# driverCorriente.net
KiCad netlist of a schematic drawn in EAGLE
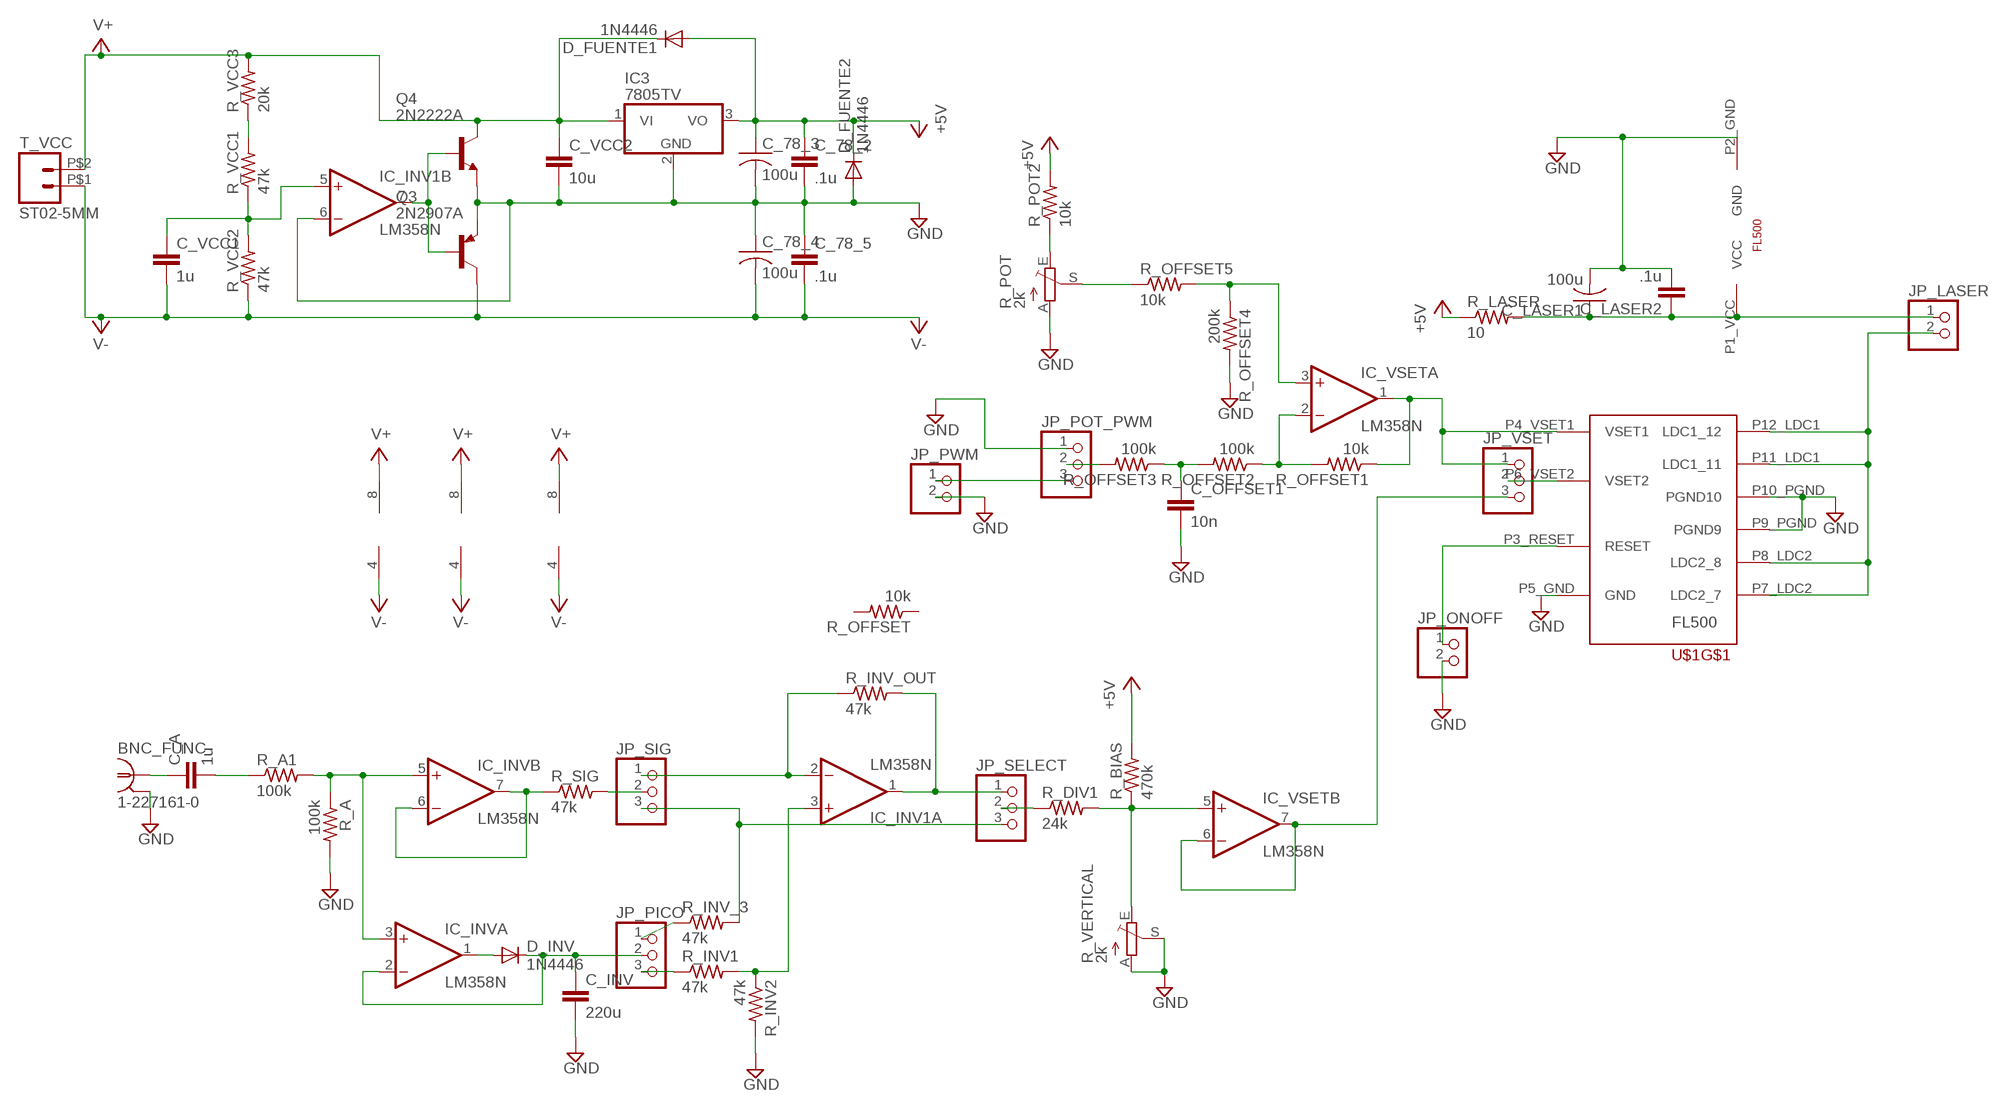
[diagram p0: schematic, sheet 1]

(export (version "E")
  (design (tool "Eeschema 10.0.6"))
  (components
    (comp (ref "BNC_FUNC")
      (value "1-227161-0")
      (footprint "eagle-import:AMP_227161")
      (fields (field (name "MF") "TYCO ELECTRONICS") (field (name "MPN") "1-227161"))
      (libsource (lib "eagle-import") (part "?2271611--0"))
    )
    (comp (ref "C_78_2")
      (value ".1u")
      (footprint "eagle-import:C050-045X075")
      (libsource (lib "eagle-import") (part "C-EU050-045X075"))
    )
    (comp (ref "C_78_3")
      (value "100u")
      (footprint "eagle-import:C050-075X075")
      (libsource (lib "eagle-import") (part "C-US050-075X075"))
    )
    (comp (ref "C_78_4")
      (value "100u")
      (footprint "eagle-import:C050-075X075")
      (libsource (lib "eagle-import") (part "C-US050-075X075"))
    )
    (comp (ref "C_78_5")
      (value ".1u")
      (footprint "eagle-import:C050-045X075")
      (libsource (lib "eagle-import") (part "C-EU050-045X075"))
    )
    (comp (ref "C_A")
      (value "1u")
      (footprint "eagle-import:C050-045X075")
      (libsource (lib "eagle-import") (part "C-EU050-045X075"))
    )
    (comp (ref "C_INV")
      (value "220u")
      (footprint "eagle-import:C050-045X075")
      (libsource (lib "eagle-import") (part "C-EU050-045X075"))
    )
    (comp (ref "C_LASER1")
      (value "100u")
      (footprint "eagle-import:C050-075X075")
      (libsource (lib "eagle-import") (part "C-US050-075X075"))
    )
    (comp (ref "C_LASER2")
      (value ".1u")
      (footprint "eagle-import:C050-045X075")
      (libsource (lib "eagle-import") (part "C-EU050-045X075"))
    )
    (comp (ref "C_OFFSET1")
      (value "10n")
      (footprint "eagle-import:C050-045X075")
      (libsource (lib "eagle-import") (part "C-EU050-045X075"))
    )
    (comp (ref "C_VCC1")
      (value "1u")
      (footprint "eagle-import:C050-045X075")
      (libsource (lib "eagle-import") (part "C-EU050-045X075"))
    )
    (comp (ref "C_VCC2")
      (value "10u")
      (footprint "eagle-import:C050-045X075")
      (libsource (lib "eagle-import") (part "C-EU050-045X075"))
    )
    (comp (ref "D_FUENTE1")
      (value "1N4446")
      (footprint "eagle-import:DO35-10")
      (libsource (lib "eagle-import") (part "1N4446"))
    )
    (comp (ref "D_FUENTE2")
      (value "1N4446")
      (footprint "eagle-import:DO35-10")
      (libsource (lib "eagle-import") (part "1N4446"))
    )
    (comp (ref "D_INV")
      (value "1N4446")
      (footprint "eagle-import:DO35-10")
      (libsource (lib "eagle-import") (part "1N4446"))
    )
    (comp (ref "IC3")
      (value "7805TV")
      (footprint "eagle-import:TO220V")
      (libsource (lib "eagle-import") (part "78TV05"))
    )
    (comp (ref "IC_INV")
      (value "LM358N")
      (footprint "eagle-import:DIL08")
      (libsource (lib "eagle-import") (part "LM358N"))
    )
    (comp (ref "IC_INV1")
      (value "LM358N")
      (footprint "eagle-import:DIL08")
      (libsource (lib "eagle-import") (part "LM358N"))
    )
    (comp (ref "IC_VSET")
      (value "LM358N")
      (footprint "eagle-import:DIL08")
      (libsource (lib "eagle-import") (part "LM358N"))
    )
    (comp (ref "JP_LASER")
      (value "PINHD-1X2")
      (footprint "eagle-import:1X02")
      (libsource (lib "eagle-import") (part "PINHD-1X2"))
    )
    (comp (ref "JP_ONOFF")
      (value "PINHD-1X2")
      (footprint "eagle-import:1X02")
      (libsource (lib "eagle-import") (part "PINHD-1X2"))
    )
    (comp (ref "JP_PICO")
      (value "PINHD-1X3")
      (footprint "eagle-import:1X03")
      (libsource (lib "eagle-import") (part "PINHD-1X3"))
    )
    (comp (ref "JP_POT_PWM")
      (value "PINHD-1X3")
      (footprint "eagle-import:1X03")
      (libsource (lib "eagle-import") (part "PINHD-1X3"))
    )
    (comp (ref "JP_PWM")
      (value "PINHD-1X2")
      (footprint "eagle-import:1X02")
      (libsource (lib "eagle-import") (part "PINHD-1X2"))
    )
    (comp (ref "JP_SELECT")
      (value "PINHD-1X3")
      (footprint "eagle-import:1X03")
      (libsource (lib "eagle-import") (part "PINHD-1X3"))
    )
    (comp (ref "JP_SIG")
      (value "PINHD-1X3")
      (footprint "eagle-import:1X03")
      (libsource (lib "eagle-import") (part "PINHD-1X3"))
    )
    (comp (ref "JP_VSET")
      (value "PINHD-1X3")
      (footprint "eagle-import:1X03")
      (libsource (lib "eagle-import") (part "PINHD-1X3"))
    )
    (comp (ref "Q3")
      (value "2N2907A")
      (footprint "eagle-import:TO18")
      (libsource (lib "eagle-import") (part "2N2907A"))
    )
    (comp (ref "Q4")
      (value "2N2222A")
      (footprint "eagle-import:TO18")
      (libsource (lib "eagle-import") (part "2N2222A"))
    )
    (comp (ref "R_A")
      (value "100k")
      (footprint "eagle-import:0207_12")
      (libsource (lib "eagle-import") (part "R-US_0207/12"))
    )
    (comp (ref "R_A1")
      (value "100k")
      (footprint "eagle-import:0207_12")
      (libsource (lib "eagle-import") (part "R-US_0207/12"))
    )
    (comp (ref "R_BIAS")
      (value "470k")
      (footprint "eagle-import:0207_12")
      (libsource (lib "eagle-import") (part "R-US_0207/12"))
    )
    (comp (ref "R_DIV1")
      (value "24k")
      (footprint "eagle-import:0207_12")
      (libsource (lib "eagle-import") (part "R-US_0207/12"))
    )
    (comp (ref "R_INV1")
      (value "47k")
      (footprint "eagle-import:0207_12")
      (libsource (lib "eagle-import") (part "R-US_0207/12"))
    )
    (comp (ref "R_INV2")
      (value "47k")
      (footprint "eagle-import:0207_12")
      (libsource (lib "eagle-import") (part "R-US_0207/12"))
    )
    (comp (ref "R_INV_3")
      (value "47k")
      (footprint "eagle-import:0207_12")
      (libsource (lib "eagle-import") (part "R-US_0207/12"))
    )
    (comp (ref "R_INV_OUT")
      (value "47k")
      (footprint "eagle-import:0207_12")
      (libsource (lib "eagle-import") (part "R-US_0207/12"))
    )
    (comp (ref "R_LASER")
      (value "10")
      (footprint "eagle-import:0207_12")
      (libsource (lib "eagle-import") (part "R-US_0207/12"))
    )
    (comp (ref "R_OFFSET")
      (value "10k")
      (footprint "eagle-import:0207_12")
      (libsource (lib "eagle-import") (part "R-US_0207/12"))
    )
    (comp (ref "R_OFFSET1")
      (value "10k")
      (footprint "eagle-import:0207_12")
      (libsource (lib "eagle-import") (part "R-US_0207/12"))
    )
    (comp (ref "R_OFFSET2")
      (value "100k")
      (footprint "eagle-import:0207_12")
      (libsource (lib "eagle-import") (part "R-US_0207/12"))
    )
    (comp (ref "R_OFFSET3")
      (value "100k")
      (footprint "eagle-import:0207_12")
      (libsource (lib "eagle-import") (part "R-US_0207/12"))
    )
    (comp (ref "R_OFFSET4")
      (value "200k")
      (footprint "eagle-import:0207_12")
      (libsource (lib "eagle-import") (part "R-US_0207/12"))
    )
    (comp (ref "R_OFFSET5")
      (value "10k")
      (footprint "eagle-import:0207_12")
      (libsource (lib "eagle-import") (part "R-US_0207/12"))
    )
    (comp (ref "R_POT")
      (value "2k")
      (footprint "eagle-import:B64Y")
      (libsource (lib "eagle-import") (part "TRIM_EU-B64Y"))
    )
    (comp (ref "R_POT2")
      (value "10k")
      (footprint "eagle-import:0207_12")
      (libsource (lib "eagle-import") (part "R-US_0207/12"))
    )
    (comp (ref "R_SIG")
      (value "47k")
      (footprint "eagle-import:0207_12")
      (libsource (lib "eagle-import") (part "R-US_0207/12"))
    )
    (comp (ref "R_VCC1")
      (value "47k")
      (footprint "eagle-import:0207_12")
      (libsource (lib "eagle-import") (part "R-US_0207/12"))
    )
    (comp (ref "R_VCC2")
      (value "47k")
      (footprint "eagle-import:0207_12")
      (libsource (lib "eagle-import") (part "R-US_0207/12"))
    )
    (comp (ref "R_VCC3")
      (value "20k")
      (footprint "eagle-import:0207_12")
      (libsource (lib "eagle-import") (part "R-US_0207/12"))
    )
    (comp (ref "R_VERTICAL")
      (value "2k")
      (footprint "eagle-import:B64Y")
      (libsource (lib "eagle-import") (part "TRIM_EU-B64Y"))
    )
    (comp (ref "T_VCC")
      (value "ST02-5MM")
      (footprint "eagle-import:EK500V-02P")
      (libsource (lib "eagle-import") (part "ST02-5MM"))
    )
    (comp (ref "U$1")
      (value "FL500")
      (footprint "eagle-import:FL500")
      (libsource (lib "eagle-import") (part "FL500"))
    )
  )
  (nets
    (net (code "1") (name "+5V") (class "Default")
      (node (ref "C_78_2") (pin "1") (pinfunction "1_1") (pintype "passive"))
      (node (ref "C_78_3") (pin "1") (pinfunction "1_1") (pintype "passive"))
      (node (ref "D_FUENTE1") (pin "A") (pinfunction "A_A") (pintype "passive"))
      (node (ref "D_FUENTE2") (pin "C") (pinfunction "C_C") (pintype "passive"))
      (node (ref "IC3") (pin "3") (pinfunction "VO_3") (pintype "passive"))
      (node (ref "R_BIAS") (pin "2") (pinfunction "2_2") (pintype "passive"))
      (node (ref "R_LASER") (pin "1") (pinfunction "1_1") (pintype "passive"))
      (node (ref "R_POT2") (pin "2") (pinfunction "2_2") (pintype "passive"))
    )
    (net (code "2") (name "GND") (class "Default")
      (node (ref "BNC_FUNC") (pin "2") (pinfunction "2_2") (pintype "passive"))
      (node (ref "C_78_2") (pin "2") (pinfunction "2_2") (pintype "passive"))
      (node (ref "C_78_3") (pin "2") (pinfunction "2_2") (pintype "passive"))
      (node (ref "C_78_4") (pin "1") (pinfunction "1_1") (pintype "passive"))
      (node (ref "C_78_5") (pin "1") (pinfunction "1_1") (pintype "passive"))
      (node (ref "C_INV") (pin "2") (pinfunction "2_2") (pintype "passive"))
      (node (ref "C_LASER1") (pin "2") (pinfunction "2_2") (pintype "passive"))
      (node (ref "C_LASER2") (pin "2") (pinfunction "2_2") (pintype "passive"))
      (node (ref "C_OFFSET1") (pin "2") (pinfunction "2_2") (pintype "passive"))
      (node (ref "C_VCC2") (pin "2") (pinfunction "2_2") (pintype "passive"))
      (node (ref "D_FUENTE2") (pin "A") (pinfunction "A_A") (pintype "passive"))
      (node (ref "IC3") (pin "2") (pinfunction "GND_2") (pintype "passive"))
      (node (ref "IC_INV1") (pin "6") (pinfunction "-IN_6") (pintype "input"))
      (node (ref "JP_ONOFF") (pin "2") (pinfunction "2_2") (pintype "passive"))
      (node (ref "JP_POT_PWM") (pin "1") (pinfunction "1_1") (pintype "passive"))
      (node (ref "JP_PWM") (pin "2") (pinfunction "2_2") (pintype "passive"))
      (node (ref "Q3") (pin "1") (pinfunction "E_1") (pintype "passive"))
      (node (ref "Q4") (pin "1") (pinfunction "E_1") (pintype "passive"))
      (node (ref "R_A") (pin "2") (pinfunction "2_2") (pintype "passive"))
      (node (ref "R_INV2") (pin "2") (pinfunction "2_2") (pintype "passive"))
      (node (ref "R_OFFSET4") (pin "2") (pinfunction "2_2") (pintype "passive"))
      (node (ref "R_POT") (pin "A") (pinfunction "A_A") (pintype "passive"))
      (node (ref "R_VERTICAL") (pin "A") (pinfunction "A_A") (pintype "passive"))
      (node (ref "R_VERTICAL") (pin "S") (pinfunction "S_S") (pintype "passive"))
      (node (ref "U$1") (pin "P10_PGND") (pinfunction "PGND10_P10_PGND") (pintype "bidirectional"))
      (node (ref "U$1") (pin "P2_GND") (pinfunction "GND_P2_GND") (pintype "bidirectional"))
      (node (ref "U$1") (pin "P5_GND") (pinfunction "GND_P5_GND") (pintype "bidirectional"))
      (node (ref "U$1") (pin "P9_PGND") (pinfunction "PGND9_P9_PGND") (pintype "bidirectional"))
    )
    (net (code "3") (name "Net-(BNC_FUNC-Pad1)") (class "Default")
      (node (ref "BNC_FUNC") (pin "1") (pinfunction "1_1") (pintype "passive"))
      (node (ref "C_A") (pin "1") (pinfunction "1_1") (pintype "passive"))
    )
    (net (code "4") (name "Net-(C_A-Pad2)") (class "Default")
      (node (ref "C_A") (pin "2") (pinfunction "2_2") (pintype "passive"))
      (node (ref "R_A1") (pin "1") (pinfunction "1_1") (pintype "passive"))
    )
    (net (code "5") (name "Net-(C_OFFSET1-Pad1)") (class "Default")
      (node (ref "C_OFFSET1") (pin "1") (pinfunction "1_1") (pintype "passive"))
      (node (ref "R_OFFSET2") (pin "2") (pinfunction "2_2") (pintype "passive"))
      (node (ref "R_OFFSET3") (pin "1") (pinfunction "1_1") (pintype "passive"))
    )
    (net (code "6") (name "Net-(IC_INV1A-+IN)") (class "Default")
      (node (ref "IC_INV1") (pin "3") (pinfunction "+IN_3") (pintype "input"))
      (node (ref "R_INV1") (pin "2") (pinfunction "2_2") (pintype "passive"))
      (node (ref "R_INV2") (pin "1") (pinfunction "1_1") (pintype "passive"))
    )
    (net (code "7") (name "Net-(IC_INV1A--IN)") (class "Default")
      (node (ref "IC_INV1") (pin "2") (pinfunction "-IN_2") (pintype "input"))
      (node (ref "JP_SIG") (pin "1") (pinfunction "1_1") (pintype "passive"))
      (node (ref "R_INV_OUT") (pin "1") (pinfunction "1_1") (pintype "passive"))
    )
    (net (code "8") (name "Net-(IC_INV1A-OUT)") (class "Default")
      (node (ref "IC_INV1") (pin "1") (pinfunction "OUT_1") (pintype "output"))
      (node (ref "JP_SELECT") (pin "1") (pinfunction "1_1") (pintype "passive"))
      (node (ref "R_INV_OUT") (pin "2") (pinfunction "2_2") (pintype "passive"))
    )
    (net (code "9") (name "Net-(IC_INV1B-+IN)") (class "Default")
      (node (ref "C_VCC1") (pin "1") (pinfunction "1_1") (pintype "passive"))
      (node (ref "IC_INV1") (pin "5") (pinfunction "+IN_5") (pintype "input"))
      (node (ref "R_VCC1") (pin "1") (pinfunction "1_1") (pintype "passive"))
      (node (ref "R_VCC2") (pin "2") (pinfunction "2_2") (pintype "passive"))
    )
    (net (code "10") (name "Net-(IC_INV1B-OUT)") (class "Default")
      (node (ref "IC_INV1") (pin "7") (pinfunction "OUT_7") (pintype "output"))
      (node (ref "Q3") (pin "2") (pinfunction "B_2") (pintype "passive"))
      (node (ref "Q4") (pin "2") (pinfunction "B_2") (pintype "passive"))
    )
    (net (code "11") (name "Net-(IC_INVA-+IN)") (class "Default")
      (node (ref "IC_INV") (pin "3") (pinfunction "+IN_3") (pintype "input"))
      (node (ref "IC_INV") (pin "5") (pinfunction "+IN_5") (pintype "input"))
      (node (ref "R_A") (pin "1") (pinfunction "1_1") (pintype "passive"))
      (node (ref "R_A1") (pin "2") (pinfunction "2_2") (pintype "passive"))
    )
    (net (code "12") (name "Net-(IC_INVA--IN)") (class "Default")
      (node (ref "C_INV") (pin "1") (pinfunction "1_1") (pintype "passive"))
      (node (ref "D_INV") (pin "C") (pinfunction "C_C") (pintype "passive"))
      (node (ref "IC_INV") (pin "2") (pinfunction "-IN_2") (pintype "input"))
      (node (ref "JP_PICO") (pin "2") (pinfunction "2_2") (pintype "passive"))
    )
    (net (code "13") (name "Net-(IC_INVA-OUT)") (class "Default")
      (node (ref "D_INV") (pin "A") (pinfunction "A_A") (pintype "passive"))
      (node (ref "IC_INV") (pin "1") (pinfunction "OUT_1") (pintype "output"))
    )
    (net (code "14") (name "Net-(IC_INVB--IN)") (class "Default")
      (node (ref "IC_INV") (pin "6") (pinfunction "-IN_6") (pintype "input"))
      (node (ref "IC_INV") (pin "7") (pinfunction "OUT_7") (pintype "output"))
      (node (ref "R_SIG") (pin "1") (pinfunction "1_1") (pintype "passive"))
    )
    (net (code "15") (name "Net-(IC_VSETA-+IN)") (class "Default")
      (node (ref "IC_VSET") (pin "3") (pinfunction "+IN_3") (pintype "input"))
      (node (ref "R_OFFSET4") (pin "1") (pinfunction "1_1") (pintype "passive"))
      (node (ref "R_OFFSET5") (pin "2") (pinfunction "2_2") (pintype "passive"))
    )
    (net (code "16") (name "Net-(IC_VSETA--IN)") (class "Default")
      (node (ref "IC_VSET") (pin "2") (pinfunction "-IN_2") (pintype "input"))
      (node (ref "R_OFFSET1") (pin "2") (pinfunction "2_2") (pintype "passive"))
      (node (ref "R_OFFSET2") (pin "1") (pinfunction "1_1") (pintype "passive"))
    )
    (net (code "17") (name "Net-(IC_VSETA-OUT)") (class "Default")
      (node (ref "IC_VSET") (pin "1") (pinfunction "OUT_1") (pintype "output"))
      (node (ref "JP_VSET") (pin "1") (pinfunction "1_1") (pintype "passive"))
      (node (ref "R_OFFSET1") (pin "1") (pinfunction "1_1") (pintype "passive"))
      (node (ref "U$1") (pin "P4_VSET1") (pinfunction "VSET1_P4_VSET1") (pintype "bidirectional"))
    )
    (net (code "18") (name "Net-(IC_VSETB-+IN)") (class "Default")
      (node (ref "IC_VSET") (pin "5") (pinfunction "+IN_5") (pintype "input"))
      (node (ref "R_BIAS") (pin "1") (pinfunction "1_1") (pintype "passive"))
      (node (ref "R_DIV1") (pin "2") (pinfunction "2_2") (pintype "passive"))
      (node (ref "R_VERTICAL") (pin "E") (pinfunction "E_E") (pintype "passive"))
    )
    (net (code "19") (name "Net-(IC_VSETB--IN)") (class "Default")
      (node (ref "IC_VSET") (pin "6") (pinfunction "-IN_6") (pintype "input"))
      (node (ref "IC_VSET") (pin "7") (pinfunction "OUT_7") (pintype "output"))
      (node (ref "JP_VSET") (pin "3") (pinfunction "3_3") (pintype "passive"))
    )
    (net (code "20") (name "Net-(JP_PICO-Pad1)") (class "Default")
      (node (ref "JP_PICO") (pin "1") (pinfunction "1_1") (pintype "passive"))
      (node (ref "R_INV_3") (pin "1") (pinfunction "1_1") (pintype "passive"))
    )
    (net (code "21") (name "Net-(JP_PICO-Pad3)") (class "Default")
      (node (ref "JP_PICO") (pin "3") (pinfunction "3_3") (pintype "passive"))
      (node (ref "R_INV1") (pin "1") (pinfunction "1_1") (pintype "passive"))
    )
    (net (code "22") (name "Net-(JP_POT_PWM-Pad2)") (class "Default")
      (node (ref "JP_POT_PWM") (pin "2") (pinfunction "2_2") (pintype "passive"))
      (node (ref "R_OFFSET3") (pin "2") (pinfunction "2_2") (pintype "passive"))
    )
    (net (code "23") (name "Net-(JP_POT_PWM-Pad3)") (class "Default")
      (node (ref "JP_POT_PWM") (pin "3") (pinfunction "3_3") (pintype "passive"))
      (node (ref "JP_PWM") (pin "1") (pinfunction "1_1") (pintype "passive"))
    )
    (net (code "24") (name "Net-(JP_SELECT-Pad2)") (class "Default")
      (node (ref "JP_SELECT") (pin "2") (pinfunction "2_2") (pintype "passive"))
      (node (ref "R_DIV1") (pin "1") (pinfunction "1_1") (pintype "passive"))
    )
    (net (code "25") (name "Net-(JP_SELECT-Pad3)") (class "Default")
      (node (ref "JP_SELECT") (pin "3") (pinfunction "3_3") (pintype "passive"))
      (node (ref "JP_SIG") (pin "3") (pinfunction "3_3") (pintype "passive"))
      (node (ref "R_INV_3") (pin "2") (pinfunction "2_2") (pintype "passive"))
    )
    (net (code "26") (name "Net-(JP_SIG-Pad2)") (class "Default")
      (node (ref "JP_SIG") (pin "2") (pinfunction "2_2") (pintype "passive"))
      (node (ref "R_SIG") (pin "2") (pinfunction "2_2") (pintype "passive"))
    )
    (net (code "27") (name "Net-(R_OFFSET5-Pad1)") (class "Default")
      (node (ref "R_OFFSET5") (pin "1") (pinfunction "1_1") (pintype "passive"))
      (node (ref "R_POT") (pin "S") (pinfunction "S_S") (pintype "passive"))
    )
    (net (code "28") (name "Net-(R_POT-PadE)") (class "Default")
      (node (ref "R_POT") (pin "E") (pinfunction "E_E") (pintype "passive"))
      (node (ref "R_POT2") (pin "1") (pinfunction "1_1") (pintype "passive"))
    )
    (net (code "29") (name "Net-(R_VCC1-Pad2)") (class "Default")
      (node (ref "R_VCC1") (pin "2") (pinfunction "2_2") (pintype "passive"))
      (node (ref "R_VCC3") (pin "1") (pinfunction "1_1") (pintype "passive"))
    )
    (net (code "30") (name "Net-(U$1A-LDC1_11)") (class "Default")
      (node (ref "JP_LASER") (pin "2") (pinfunction "2_2") (pintype "passive"))
      (node (ref "U$1") (pin "P11_LDC1") (pinfunction "LDC1_11_P11_LDC1") (pintype "bidirectional"))
      (node (ref "U$1") (pin "P12_LDC1") (pinfunction "LDC1_12_P12_LDC1") (pintype "bidirectional"))
      (node (ref "U$1") (pin "P7_LDC2") (pinfunction "LDC2_7_P7_LDC2") (pintype "bidirectional"))
      (node (ref "U$1") (pin "P8_LDC2") (pinfunction "LDC2_8_P8_LDC2") (pintype "bidirectional"))
    )
    (net (code "31") (name "Net-(U$1A-RESET)") (class "Default")
      (node (ref "JP_ONOFF") (pin "1") (pinfunction "1_1") (pintype "passive"))
      (node (ref "U$1") (pin "P3_RESET") (pinfunction "RESET_P3_RESET") (pintype "bidirectional"))
    )
    (net (code "32") (name "Net-(U$1A-VSET2)") (class "Default")
      (node (ref "JP_VSET") (pin "2") (pinfunction "2_2") (pintype "passive"))
      (node (ref "U$1") (pin "P6_VSET2") (pinfunction "VSET2_P6_VSET2") (pintype "bidirectional"))
    )
    (net (code "33") (name "Net-(U$1B-VCC)") (class "Default")
      (node (ref "C_LASER1") (pin "1") (pinfunction "1_1") (pintype "passive"))
      (node (ref "C_LASER2") (pin "1") (pinfunction "1_1") (pintype "passive"))
      (node (ref "JP_LASER") (pin "1") (pinfunction "1_1") (pintype "passive"))
      (node (ref "R_LASER") (pin "2") (pinfunction "2_2") (pintype "passive"))
      (node (ref "U$1") (pin "P1_VCC") (pinfunction "VCC_P1_VCC") (pintype "bidirectional"))
    )
    (net (code "34") (name "V+") (class "Default")
      (node (ref "C_VCC2") (pin "1") (pinfunction "1_1") (pintype "passive"))
      (node (ref "D_FUENTE1") (pin "C") (pinfunction "C_C") (pintype "passive"))
      (node (ref "IC3") (pin "1") (pinfunction "VI_1") (pintype "input"))
      (node (ref "IC_INV") (pin "8") (pinfunction "V+_8") (pintype "power_in"))
      (node (ref "IC_INV1") (pin "8") (pinfunction "V+_8") (pintype "power_in"))
      (node (ref "IC_VSET") (pin "8") (pinfunction "V+_8") (pintype "power_in"))
      (node (ref "Q4") (pin "3") (pinfunction "C_3") (pintype "passive"))
      (node (ref "R_VCC3") (pin "2") (pinfunction "2_2") (pintype "passive"))
      (node (ref "T_VCC") (pin "P$2") (pinfunction "2_P$2") (pintype "passive"))
    )
    (net (code "35") (name "V-") (class "Default")
      (node (ref "C_78_4") (pin "2") (pinfunction "2_2") (pintype "passive"))
      (node (ref "C_78_5") (pin "2") (pinfunction "2_2") (pintype "passive"))
      (node (ref "C_VCC1") (pin "2") (pinfunction "2_2") (pintype "passive"))
      (node (ref "IC_INV") (pin "4") (pinfunction "V-_4") (pintype "power_in"))
      (node (ref "IC_INV1") (pin "4") (pinfunction "V-_4") (pintype "power_in"))
      (node (ref "IC_VSET") (pin "4") (pinfunction "V-_4") (pintype "power_in"))
      (node (ref "Q3") (pin "3") (pinfunction "C_3") (pintype "passive"))
      (node (ref "R_VCC2") (pin "1") (pinfunction "1_1") (pintype "passive"))
      (node (ref "T_VCC") (pin "P$1") (pinfunction "1_P$1") (pintype "passive"))
    )
    (net (code "36") (name "unconnected-(R_OFFSET-Pad1)") (class "Default")
      (node (ref "R_OFFSET") (pin "1") (pinfunction "1_1") (pintype "passive"))
    )
    (net (code "37") (name "unconnected-(R_OFFSET-Pad2)") (class "Default")
      (node (ref "R_OFFSET") (pin "2") (pinfunction "2_2") (pintype "passive"))
    )
  )
)
